# EEG_AFE_Sheet_1.net
KiCad netlist of a schematic drawn in Altium Designer
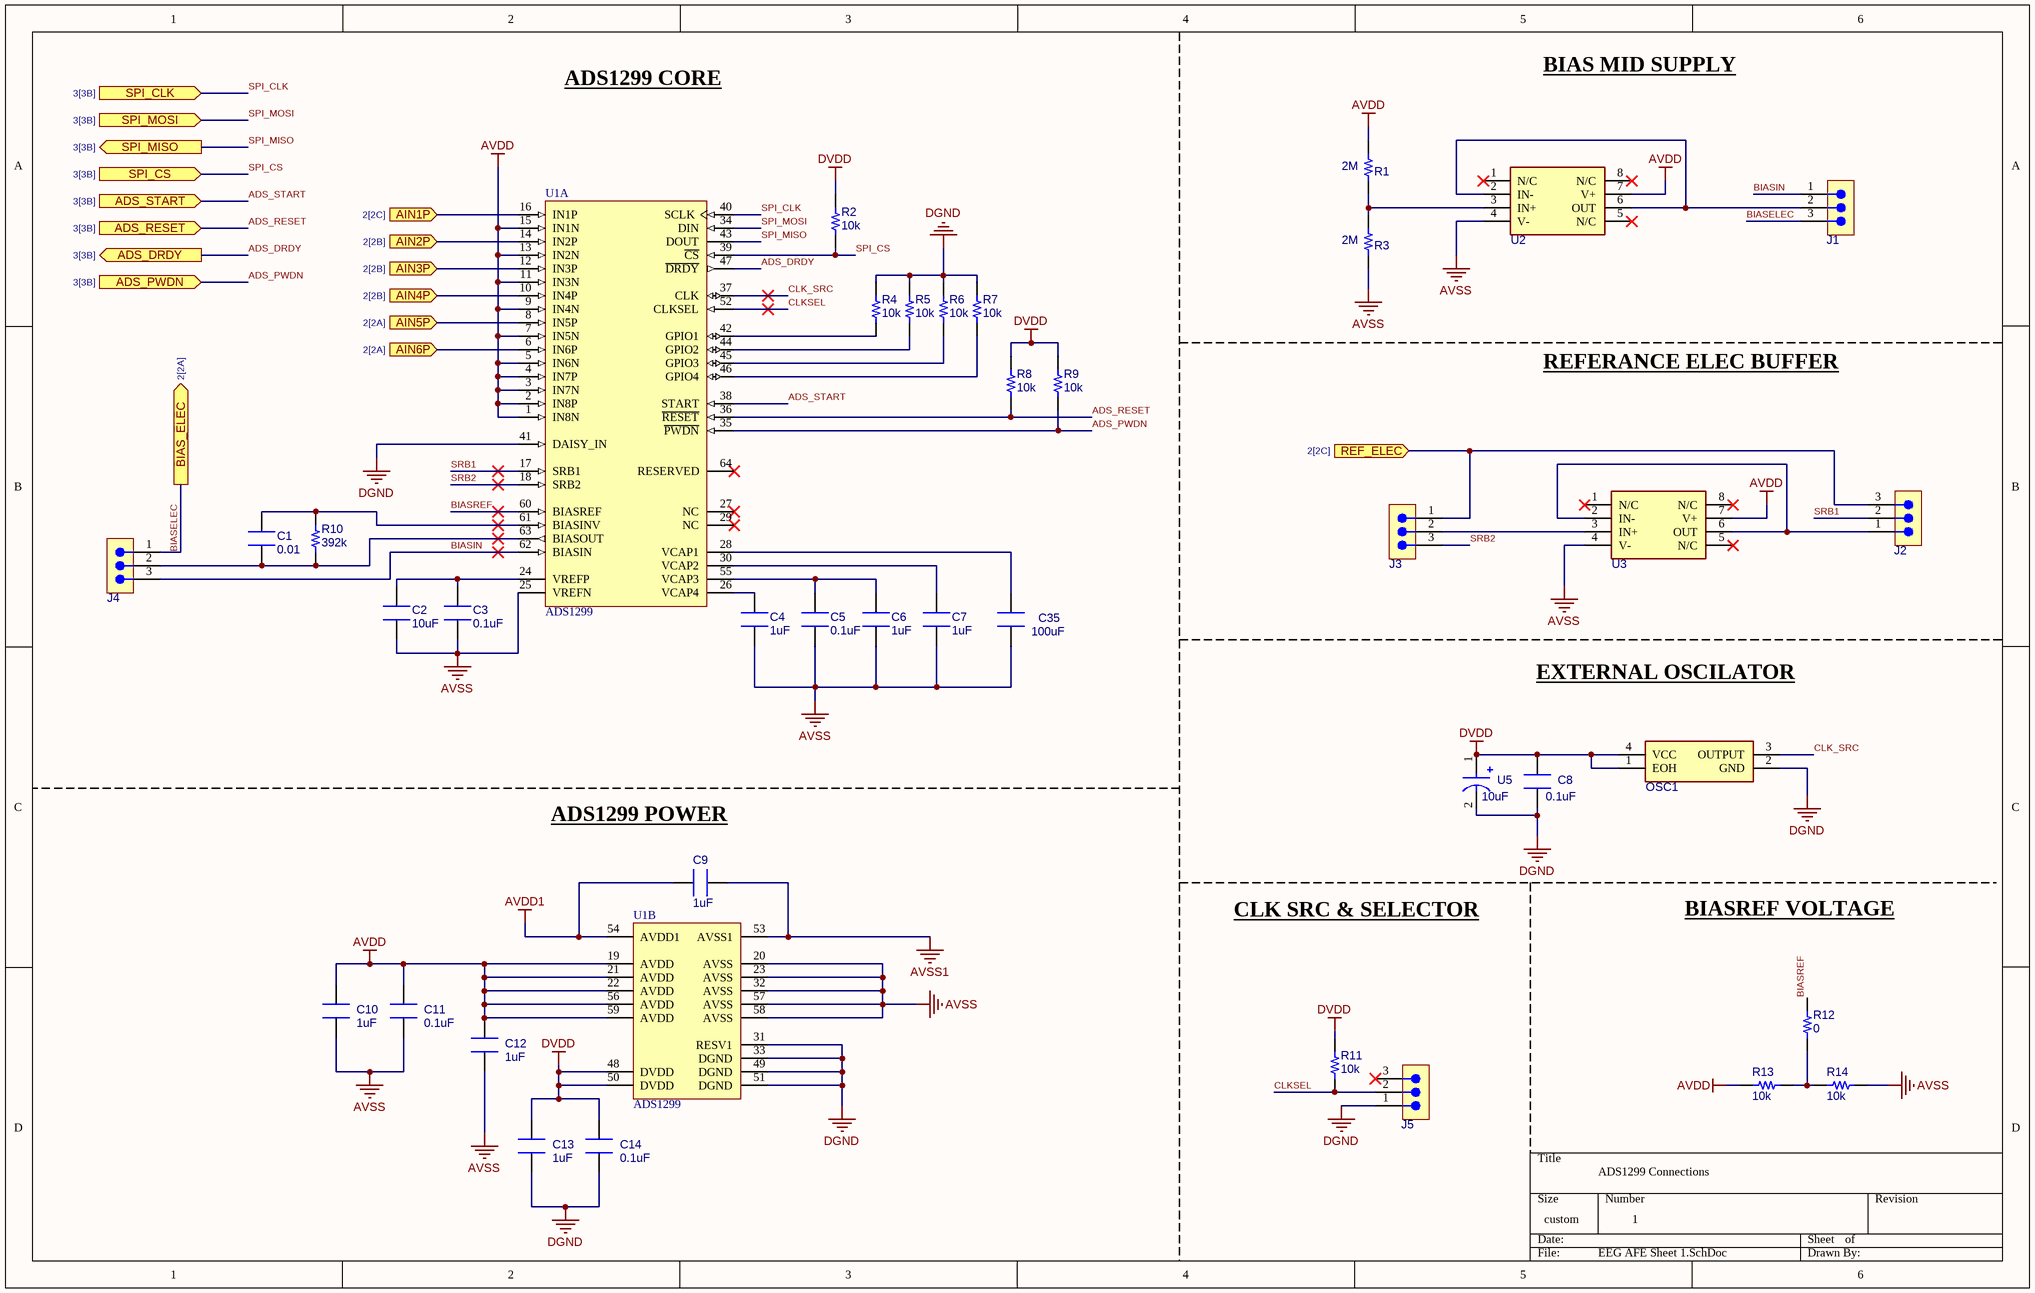
[diagram p0: EEG AFE Sheet 1.SchDoc]

(export (version "E")
  (design (tool "Eeschema 10.0.6"))
  (components
    (comp (ref "C1")
      (value "0.01")
      (footprint "CAP 0603_1608")
      (fields (field (name "MANUFACTURER") "???") (field (name "MANUFACTURER PART NUMBER") "08055C104KAT2A"))
      (libsource (lib "Schlib") (part "08055C104KAT2A"))
    )
    (comp (ref "C2")
      (value "10uF")
      (footprint "CAP0805")
      (fields (field (name "MANUFACTURER") "???") (field (name "MANUFACTURER PART NUMBER") "08055C104KAT2A"))
      (libsource (lib "Schlib") (part "08055C104KAT2A"))
    )
    (comp (ref "C3")
      (value "0.1uF")
      (footprint "CAP 0603_1608")
      (fields (field (name "MANUFACTURER") "???") (field (name "MANUFACTURER PART NUMBER") "08055C104KAT2A"))
      (libsource (lib "Schlib") (part "08055C104KAT2A"))
    )
    (comp (ref "C4")
      (value "1uF")
      (footprint "CAP 0603_1608")
      (fields (field (name "MANUFACTURER") "???") (field (name "MANUFACTURER PART NUMBER") "08055C104KAT2A"))
      (libsource (lib "Schlib") (part "08055C104KAT2A"))
    )
    (comp (ref "C5")
      (value "0.1uF")
      (footprint "CAP 0603_1608")
      (fields (field (name "MANUFACTURER") "???") (field (name "MANUFACTURER PART NUMBER") "08055C104KAT2A"))
      (libsource (lib "Schlib") (part "08055C104KAT2A"))
    )
    (comp (ref "C6")
      (value "1uF")
      (footprint "CAP 0603_1608")
      (fields (field (name "MANUFACTURER") "???") (field (name "MANUFACTURER PART NUMBER") "08055C104KAT2A"))
      (libsource (lib "Schlib") (part "08055C104KAT2A"))
    )
    (comp (ref "C7")
      (value "1uF")
      (footprint "CAP 0603_1608")
      (fields (field (name "MANUFACTURER") "???") (field (name "MANUFACTURER PART NUMBER") "08055C104KAT2A"))
      (libsource (lib "Schlib") (part "08055C104KAT2A"))
    )
    (comp (ref "C8")
      (value "0.1uF")
      (footprint "CAP 0603_1608")
      (fields (field (name "MANUFACTURER") "???") (field (name "MANUFACTURER PART NUMBER") "08055C104KAT2A"))
      (libsource (lib "Schlib") (part "08055C104KAT2A"))
    )
    (comp (ref "C9")
      (value "1uF")
      (footprint "CAP 0603_1608")
      (fields (field (name "MANUFACTURER") "???") (field (name "MANUFACTURER PART NUMBER") "08055C104KAT2A"))
      (libsource (lib "Schlib") (part "08055C104KAT2A"))
    )
    (comp (ref "C10")
      (value "1uF")
      (footprint "CAP 0603_1608")
      (fields (field (name "MANUFACTURER") "???") (field (name "MANUFACTURER PART NUMBER") "08055C104KAT2A"))
      (libsource (lib "Schlib") (part "08055C104KAT2A"))
    )
    (comp (ref "C11")
      (value "0.1uF")
      (footprint "CAP 0603_1608")
      (fields (field (name "MANUFACTURER") "???") (field (name "MANUFACTURER PART NUMBER") "08055C104KAT2A"))
      (libsource (lib "Schlib") (part "08055C104KAT2A"))
    )
    (comp (ref "C12")
      (value "1uF")
      (footprint "CAP 0603_1608")
      (fields (field (name "MANUFACTURER") "???") (field (name "MANUFACTURER PART NUMBER") "08055C104KAT2A"))
      (libsource (lib "Schlib") (part "08055C104KAT2A"))
    )
    (comp (ref "C13")
      (value "1uF")
      (footprint "CAP 0603_1608")
      (fields (field (name "MANUFACTURER") "???") (field (name "MANUFACTURER PART NUMBER") "08055C104KAT2A"))
      (libsource (lib "Schlib") (part "08055C104KAT2A"))
    )
    (comp (ref "C14")
      (value "0.1uF")
      (footprint "CAP 0603_1608")
      (fields (field (name "MANUFACTURER") "???") (field (name "MANUFACTURER PART NUMBER") "08055C104KAT2A"))
      (libsource (lib "Schlib") (part "08055C104KAT2A"))
    )
    (comp (ref "C35")
      (value "100uF")
      (footprint "CAP1210")
      (fields
        (field (name "MANUFACTURER") "???")
        (field (name "MANUFACTURER PART NUMBER") "CL32A107MPVNNNE")
        (field (name "PUBLISHER") "Paraqum Technologies")
      )
      (libsource (lib "Schlib") (part "CL32A107MPVNNNE"))
    )
    (comp (ref "J1")
      (value "*")
      (footprint "SMTC-TSW-103-07-X-S")
      (fields
        (field (name "MANUFACTURER") "???")
        (field (name "MANUFACTURER PART NUMBER") "TSW-103-07-T-S")
        (field (name "PUBLISHER") "Paraqum Technologies")
      )
      (libsource (lib "") (part "TSW-103-07-T-S_2"))
    )
    (comp (ref "J2")
      (value "*")
      (footprint "SMTC-TSW-103-07-X-S")
      (fields
        (field (name "MANUFACTURER") "???")
        (field (name "MANUFACTURER PART NUMBER") "TSW-103-07-T-S")
        (field (name "PUBLISHER") "Paraqum Technologies")
      )
      (libsource (lib "Schlib") (part "TSW-103-07-T-S"))
    )
    (comp (ref "J3")
      (value "*")
      (footprint "SMTC-TSW-103-07-X-S")
      (fields
        (field (name "MANUFACTURER") "???")
        (field (name "MANUFACTURER PART NUMBER") "TSW-103-07-T-S")
        (field (name "PUBLISHER") "Paraqum Technologies")
      )
      (libsource (lib "") (part "TSW-103-07-T-S_1"))
    )
    (comp (ref "J4")
      (value "*")
      (footprint "SMTC-TSW-103-07-X-S")
      (fields
        (field (name "MANUFACTURER") "???")
        (field (name "MANUFACTURER PART NUMBER") "TSW-103-07-T-S")
        (field (name "PUBLISHER") "Paraqum Technologies")
      )
      (libsource (lib "") (part "TSW-103-07-T-S_1"))
    )
    (comp (ref "J5")
      (value "*")
      (footprint "SMTC-TSW-103-07-X-S")
      (fields
        (field (name "MANUFACTURER") "???")
        (field (name "MANUFACTURER PART NUMBER") "TSW-103-07-T-S")
        (field (name "PUBLISHER") "Paraqum Technologies")
      )
      (libsource (lib "Schlib") (part "TSW-103-07-T-S"))
    )
    (comp (ref "OSC1")
      (value "*")
      (footprint "632L3I002M04800")
      (description "Standard Clock Oscillators 2.048MHz 3.3V 50ppm")
      (fields
        (field (name "MANUFACTURER") "???")
        (field (name "MANUFACTURER PART NUMBER") "632L3I002M04800")
        (field (name "PUBLISHER") "Paraqum Technologies")
      )
      (libsource (lib "Schlib") (part "632L3I002M04800"))
    )
    (comp (ref "R1")
      (value "2M")
      (footprint "RES 0603_1608")
      (fields
        (field (name "MANUFACTURER") "???")
        (field (name "MANUFACTURER PART NUMBER") "RC0805FR-0710KL")
        (field (name "PUBLISHER") "Paraqum Technologies")
      )
      (libsource (lib "Schlib") (part "RC0805FR-0710KL"))
    )
    (comp (ref "R2")
      (value "10k")
      (footprint "RES 0603_1608")
      (fields
        (field (name "MANUFACTURER") "???")
        (field (name "MANUFACTURER PART NUMBER") "RC0805FR-0710KL")
        (field (name "PUBLISHER") "Paraqum Technologies")
      )
      (libsource (lib "Schlib") (part "RC0805FR-0710KL"))
    )
    (comp (ref "R3")
      (value "2M")
      (footprint "RES 0603_1608")
      (fields
        (field (name "MANUFACTURER") "???")
        (field (name "MANUFACTURER PART NUMBER") "RC0805FR-0710KL")
        (field (name "PUBLISHER") "Paraqum Technologies")
      )
      (libsource (lib "Schlib") (part "RC0805FR-0710KL"))
    )
    (comp (ref "R4")
      (value "10k")
      (footprint "RES 0603_1608")
      (fields
        (field (name "MANUFACTURER") "???")
        (field (name "MANUFACTURER PART NUMBER") "RC0805FR-0710KL")
        (field (name "PUBLISHER") "Paraqum Technologies")
      )
      (libsource (lib "Schlib") (part "RC0805FR-0710KL"))
    )
    (comp (ref "R5")
      (value "10k")
      (footprint "RES 0603_1608")
      (fields
        (field (name "MANUFACTURER") "???")
        (field (name "MANUFACTURER PART NUMBER") "RC0805FR-0710KL")
        (field (name "PUBLISHER") "Paraqum Technologies")
      )
      (libsource (lib "Schlib") (part "RC0805FR-0710KL"))
    )
    (comp (ref "R6")
      (value "10k")
      (footprint "RES 0603_1608")
      (fields
        (field (name "MANUFACTURER") "???")
        (field (name "MANUFACTURER PART NUMBER") "RC0805FR-0710KL")
        (field (name "PUBLISHER") "Paraqum Technologies")
      )
      (libsource (lib "Schlib") (part "RC0805FR-0710KL"))
    )
    (comp (ref "R7")
      (value "10k")
      (footprint "RES 0603_1608")
      (fields
        (field (name "MANUFACTURER") "???")
        (field (name "MANUFACTURER PART NUMBER") "RC0805FR-0710KL")
        (field (name "PUBLISHER") "Paraqum Technologies")
      )
      (libsource (lib "Schlib") (part "RC0805FR-0710KL"))
    )
    (comp (ref "R8")
      (value "10k")
      (footprint "RES 0603_1608")
      (fields
        (field (name "MANUFACTURER") "???")
        (field (name "MANUFACTURER PART NUMBER") "RC0805FR-0710KL")
        (field (name "PUBLISHER") "Paraqum Technologies")
      )
      (libsource (lib "Schlib") (part "RC0805FR-0710KL"))
    )
    (comp (ref "R9")
      (value "10k")
      (footprint "RES 0603_1608")
      (fields
        (field (name "MANUFACTURER") "???")
        (field (name "MANUFACTURER PART NUMBER") "RC0805FR-0710KL")
        (field (name "PUBLISHER") "Paraqum Technologies")
      )
      (libsource (lib "Schlib") (part "RC0805FR-0710KL"))
    )
    (comp (ref "R10")
      (value "392k")
      (footprint "RES 0603_1608")
      (fields
        (field (name "MANUFACTURER") "???")
        (field (name "MANUFACTURER PART NUMBER") "RC0805FR-0710KL")
        (field (name "PUBLISHER") "Paraqum Technologies")
      )
      (libsource (lib "Schlib") (part "RC0805FR-0710KL"))
    )
    (comp (ref "R11")
      (value "10k")
      (footprint "RES 0603_1608")
      (fields
        (field (name "MANUFACTURER") "???")
        (field (name "MANUFACTURER PART NUMBER") "RC0805FR-0710KL")
        (field (name "PUBLISHER") "Paraqum Technologies")
      )
      (libsource (lib "Schlib") (part "RC0805FR-0710KL"))
    )
    (comp (ref "R12")
      (value "0")
      (footprint "RES 0603_1608")
      (fields
        (field (name "MANUFACTURER") "???")
        (field (name "MANUFACTURER PART NUMBER") "RC0805FR-0710KL")
        (field (name "PUBLISHER") "Paraqum Technologies")
      )
      (libsource (lib "Schlib") (part "RC0805FR-0710KL"))
    )
    (comp (ref "R13")
      (value "10k")
      (footprint "RES 0603_1608")
      (fields
        (field (name "MANUFACTURER") "???")
        (field (name "MANUFACTURER PART NUMBER") "RC0805FR-0710KL")
        (field (name "PUBLISHER") "Paraqum Technologies")
      )
      (libsource (lib "Schlib") (part "RC0805FR-0710KL"))
    )
    (comp (ref "R14")
      (value "10k")
      (footprint "RES 0603_1608")
      (fields
        (field (name "MANUFACTURER") "???")
        (field (name "MANUFACTURER PART NUMBER") "RC0805FR-0710KL")
        (field (name "PUBLISHER") "Paraqum Technologies")
      )
      (libsource (lib "Schlib") (part "RC0805FR-0710KL"))
    )
    (comp (ref "U1")
      (value "ADS1299")
      (footprint "TI-PAG64_N")
      (libsource (lib "") (part "TI-ADS1299-PAG-64_1"))
    )
    (comp (ref "U2")
      (value "*")
      (footprint "SOIC127P600X175-8N")
      (description "Operational Amplifier, 1 Func, 25uV Offset-Max, CMOS, PDSO8")
      (fields
        (field (name "MANUFACTURER") "???")
        (field (name "MANUFACTURER PART NUMBER") "OPA376AIDR")
        (field (name "PUBLISHER") "Paraqum Technologies")
      )
      (libsource (lib "Schlib") (part "OPA376AIDR"))
    )
    (comp (ref "U3")
      (value "*")
      (footprint "SOIC127P600X175-8N")
      (description "Operational Amplifier, 1 Func, 25uV Offset-Max, CMOS, PDSO8")
      (fields
        (field (name "MANUFACTURER") "???")
        (field (name "MANUFACTURER PART NUMBER") "OPA376AIDR")
        (field (name "PUBLISHER") "Paraqum Technologies")
      )
      (libsource (lib "Schlib") (part "OPA376AIDR"))
    )
    (comp (ref "U5")
      (value "10uF")
      (footprint "CAPC0805_TANT")
      (fields
        (field (name "MANUFACTURER") "???")
        (field (name "MANUFACTURER PART NUMBER") "TPSR105K025R4000")
        (field (name "PUBLISHER") "Paraqum Technologies")
      )
      (libsource (lib "Schlib") (part "TPSR105K025R4000"))
    )
  )
  (nets
    (net (code "1") (name "/ADS_DRDY") (class "Default")
      (node (ref "U1") (pin "47") (pinfunction "~{DRDY}_47") (pintype "output"))
    )
    (net (code "2") (name "/ADS_PWDN") (class "Default")
      (node (ref "R9") (pin "2") (pinfunction "2_2") (pintype "passive"))
      (node (ref "U1") (pin "35") (pinfunction "~{PWDN}_35") (pintype "input"))
    )
    (net (code "3") (name "/ADS_RESET") (class "Default")
      (node (ref "R8") (pin "2") (pinfunction "2_2") (pintype "passive"))
      (node (ref "U1") (pin "36") (pinfunction "~{RESET}_36") (pintype "input"))
    )
    (net (code "4") (name "/ADS_START") (class "Default")
      (node (ref "U1") (pin "38") (pinfunction "START_38") (pintype "input"))
    )
    (net (code "5") (name "/AIN1P") (class "Default")
      (node (ref "U1") (pin "16") (pinfunction "IN1P_16") (pintype "input"))
    )
    (net (code "6") (name "/AIN2P") (class "Default")
      (node (ref "U1") (pin "14") (pinfunction "IN2P_14") (pintype "input"))
    )
    (net (code "7") (name "/AIN3P") (class "Default")
      (node (ref "U1") (pin "12") (pinfunction "IN3P_12") (pintype "input"))
    )
    (net (code "8") (name "/AIN4P") (class "Default")
      (node (ref "U1") (pin "10") (pinfunction "IN4P_10") (pintype "input"))
    )
    (net (code "9") (name "/AIN5P") (class "Default")
      (node (ref "U1") (pin "8") (pinfunction "IN5P_8") (pintype "input"))
    )
    (net (code "10") (name "/AIN6P") (class "Default")
      (node (ref "U1") (pin "6") (pinfunction "IN6P_6") (pintype "input"))
    )
    (net (code "11") (name "/BIASELEC") (class "Default")
      (node (ref "J1") (pin "3") (pinfunction "3_3") (pintype "passive"))
      (node (ref "J4") (pin "1") (pinfunction "1_1") (pintype "passive"))
    )
    (net (code "12") (name "/BIASIN") (class "Default")
      (node (ref "J1") (pin "1") (pinfunction "1_1") (pintype "passive"))
      (node (ref "J4") (pin "3") (pinfunction "3_3") (pintype "passive"))
      (node (ref "U1") (pin "62") (pinfunction "BIASIN_62") (pintype "input"))
    )
    (net (code "13") (name "/BIASREF") (class "Default")
      (node (ref "R12") (pin "1") (pinfunction "1_1") (pintype "passive"))
      (node (ref "U1") (pin "60") (pinfunction "BIASREF_60") (pintype "input"))
    )
    (net (code "14") (name "/CLKSEL") (class "Default")
      (node (ref "J5") (pin "2") (pinfunction "2_2") (pintype "passive"))
      (node (ref "R11") (pin "1") (pinfunction "1_1") (pintype "passive"))
      (node (ref "U1") (pin "52") (pinfunction "CLKSEL_52") (pintype "input"))
    )
    (net (code "15") (name "/CLK_SRC") (class "Default")
      (node (ref "OSC1") (pin "3") (pinfunction "OUTPUT_3") (pintype "passive"))
      (node (ref "U1") (pin "37") (pinfunction "CLK_37") (pintype "bidirectional"))
    )
    (net (code "16") (name "/REF_ELEC") (class "Default")
      (node (ref "J2") (pin "3") (pinfunction "3_3") (pintype "passive"))
      (node (ref "J3") (pin "1") (pinfunction "1_1") (pintype "passive"))
    )
    (net (code "17") (name "/SPI_CLK") (class "Default")
      (node (ref "U1") (pin "40") (pinfunction "SCLK_40") (pintype "input"))
    )
    (net (code "18") (name "/SPI_CS") (class "Default")
      (node (ref "R2") (pin "1") (pinfunction "1_1") (pintype "passive"))
      (node (ref "U1") (pin "39") (pinfunction "~{CS}_39") (pintype "input"))
    )
    (net (code "19") (name "/SPI_MISO") (class "Default")
      (node (ref "U1") (pin "43") (pinfunction "DOUT_43") (pintype "tri_state"))
    )
    (net (code "20") (name "/SPI_MOSI") (class "Default")
      (node (ref "U1") (pin "34") (pinfunction "DIN_34") (pintype "input"))
    )
    (net (code "21") (name "/SRB1") (class "Default")
      (node (ref "J2") (pin "2") (pinfunction "2_2") (pintype "passive"))
      (node (ref "U1") (pin "17") (pinfunction "SRB1_17") (pintype "input"))
    )
    (net (code "22") (name "/SRB2") (class "Default")
      (node (ref "J3") (pin "3") (pinfunction "3_3") (pintype "passive"))
      (node (ref "U1") (pin "18") (pinfunction "SRB2_18") (pintype "input"))
    )
    (net (code "23") (name "AVDD") (class "Default")
      (node (ref "C10") (pin "2") (pinfunction "2_2") (pintype "passive"))
      (node (ref "C11") (pin "2") (pinfunction "2_2") (pintype "passive"))
      (node (ref "C12") (pin "2") (pinfunction "2_2") (pintype "passive"))
      (node (ref "R1") (pin "2") (pinfunction "2_2") (pintype "passive"))
      (node (ref "R13") (pin "2") (pinfunction "2_2") (pintype "passive"))
      (node (ref "U1") (pin "1") (pinfunction "IN8N_1") (pintype "input"))
      (node (ref "U1") (pin "11") (pinfunction "IN3N_11") (pintype "input"))
      (node (ref "U1") (pin "13") (pinfunction "IN2N_13") (pintype "input"))
      (node (ref "U1") (pin "15") (pinfunction "IN1N_15") (pintype "input"))
      (node (ref "U1") (pin "19") (pinfunction "AVDD_19") (pintype "power_in"))
      (node (ref "U1") (pin "2") (pinfunction "IN8P_2") (pintype "input"))
      (node (ref "U1") (pin "21") (pinfunction "AVDD_21") (pintype "power_in"))
      (node (ref "U1") (pin "22") (pinfunction "AVDD_22") (pintype "power_in"))
      (node (ref "U1") (pin "3") (pinfunction "IN7N_3") (pintype "input"))
      (node (ref "U1") (pin "4") (pinfunction "IN7P_4") (pintype "input"))
      (node (ref "U1") (pin "5") (pinfunction "IN6N_5") (pintype "input"))
      (node (ref "U1") (pin "56") (pinfunction "AVDD_56") (pintype "power_in"))
      (node (ref "U1") (pin "59") (pinfunction "AVDD_59") (pintype "power_in"))
      (node (ref "U1") (pin "7") (pinfunction "IN5N_7") (pintype "input"))
      (node (ref "U1") (pin "9") (pinfunction "IN4N_9") (pintype "input"))
      (node (ref "U2") (pin "7") (pinfunction "V+_7") (pintype "passive"))
      (node (ref "U3") (pin "7") (pinfunction "V+_7") (pintype "passive"))
    )
    (net (code "24") (name "AVDD1") (class "Default")
      (node (ref "C9") (pin "2") (pinfunction "2_2") (pintype "passive"))
      (node (ref "U1") (pin "54") (pinfunction "AVDD1_54") (pintype "power_in"))
    )
    (net (code "25") (name "AVSS") (class "Default")
      (node (ref "C10") (pin "1") (pinfunction "1_1") (pintype "passive"))
      (node (ref "C11") (pin "1") (pinfunction "1_1") (pintype "passive"))
      (node (ref "C12") (pin "1") (pinfunction "1_1") (pintype "passive"))
      (node (ref "C2") (pin "2") (pinfunction "2_2") (pintype "passive"))
      (node (ref "C3") (pin "2") (pinfunction "2_2") (pintype "passive"))
      (node (ref "C35") (pin "1") (pinfunction "1_1") (pintype "passive"))
      (node (ref "C4") (pin "2") (pinfunction "2_2") (pintype "passive"))
      (node (ref "C5") (pin "2") (pinfunction "2_2") (pintype "passive"))
      (node (ref "C6") (pin "2") (pinfunction "2_2") (pintype "passive"))
      (node (ref "C7") (pin "2") (pinfunction "2_2") (pintype "passive"))
      (node (ref "R14") (pin "1") (pinfunction "1_1") (pintype "passive"))
      (node (ref "R3") (pin "1") (pinfunction "1_1") (pintype "passive"))
      (node (ref "U1") (pin "20") (pinfunction "AVSS_20") (pintype "power_in"))
      (node (ref "U1") (pin "23") (pinfunction "AVSS_23") (pintype "power_in"))
      (node (ref "U1") (pin "25") (pinfunction "VREFN_25") (pintype "passive"))
      (node (ref "U1") (pin "32") (pinfunction "AVSS_32") (pintype "power_in"))
      (node (ref "U1") (pin "57") (pinfunction "AVSS_57") (pintype "power_in"))
      (node (ref "U1") (pin "58") (pinfunction "AVSS_58") (pintype "power_in"))
      (node (ref "U2") (pin "4") (pinfunction "V-_4") (pintype "passive"))
      (node (ref "U3") (pin "4") (pinfunction "V-_4") (pintype "passive"))
    )
    (net (code "26") (name "AVSS1") (class "Default")
      (node (ref "C9") (pin "1") (pinfunction "1_1") (pintype "passive"))
      (node (ref "U1") (pin "53") (pinfunction "AVSS1_53") (pintype "power_in"))
    )
    (net (code "27") (name "DGND") (class "Default")
      (node (ref "C13") (pin "1") (pinfunction "1_1") (pintype "passive"))
      (node (ref "C14") (pin "1") (pinfunction "1_1") (pintype "passive"))
      (node (ref "C8") (pin "1") (pinfunction "1_1") (pintype "passive"))
      (node (ref "J5") (pin "1") (pinfunction "1_1") (pintype "passive"))
      (node (ref "OSC1") (pin "2") (pinfunction "GND_2") (pintype "passive"))
      (node (ref "R4") (pin "2") (pinfunction "2_2") (pintype "passive"))
      (node (ref "R5") (pin "2") (pinfunction "2_2") (pintype "passive"))
      (node (ref "R6") (pin "2") (pinfunction "2_2") (pintype "passive"))
      (node (ref "R7") (pin "2") (pinfunction "2_2") (pintype "passive"))
      (node (ref "U1") (pin "31") (pinfunction "RESV1_31") (pintype "power_in"))
      (node (ref "U1") (pin "33") (pinfunction "DGND_33") (pintype "power_in"))
      (node (ref "U1") (pin "41") (pinfunction "DAISY_IN_41") (pintype "input"))
      (node (ref "U1") (pin "49") (pinfunction "DGND_49") (pintype "power_in"))
      (node (ref "U1") (pin "51") (pinfunction "DGND_51") (pintype "power_in"))
      (node (ref "U5") (pin "2") (pinfunction "A_2") (pintype "passive"))
    )
    (net (code "28") (name "DVDD") (class "Default")
      (node (ref "C13") (pin "2") (pinfunction "2_2") (pintype "passive"))
      (node (ref "C14") (pin "2") (pinfunction "2_2") (pintype "passive"))
      (node (ref "C8") (pin "2") (pinfunction "2_2") (pintype "passive"))
      (node (ref "OSC1") (pin "1") (pinfunction "EOH_1") (pintype "passive"))
      (node (ref "OSC1") (pin "4") (pinfunction "VCC_4") (pintype "passive"))
      (node (ref "R11") (pin "2") (pinfunction "2_2") (pintype "passive"))
      (node (ref "R2") (pin "2") (pinfunction "2_2") (pintype "passive"))
      (node (ref "R8") (pin "1") (pinfunction "1_1") (pintype "passive"))
      (node (ref "R9") (pin "1") (pinfunction "1_1") (pintype "passive"))
      (node (ref "U1") (pin "48") (pinfunction "DVDD_48") (pintype "power_in"))
      (node (ref "U1") (pin "50") (pinfunction "DVDD_50") (pintype "power_in"))
      (node (ref "U5") (pin "1") (pinfunction "C_1") (pintype "passive"))
    )
    (net (code "29") (name "Net-(R12-Pad2)") (class "Default")
      (node (ref "R12") (pin "2") (pinfunction "2_2") (pintype "passive"))
      (node (ref "R13") (pin "1") (pinfunction "1_1") (pintype "passive"))
      (node (ref "R14") (pin "2") (pinfunction "2_2") (pintype "passive"))
    )
    (net (code "30") (name "Net-(U1A-BIASINV)") (class "Default")
      (node (ref "C1") (pin "1") (pinfunction "1_1") (pintype "passive"))
      (node (ref "R10") (pin "1") (pinfunction "1_1") (pintype "passive"))
      (node (ref "U1") (pin "61") (pinfunction "BIASINV_61") (pintype "input"))
    )
    (net (code "31") (name "Net-(U1A-BIASOUT)") (class "Default")
      (node (ref "C1") (pin "2") (pinfunction "2_2") (pintype "passive"))
      (node (ref "J4") (pin "2") (pinfunction "2_2") (pintype "passive"))
      (node (ref "R10") (pin "2") (pinfunction "2_2") (pintype "passive"))
      (node (ref "U1") (pin "63") (pinfunction "BIASOUT_63") (pintype "output"))
    )
    (net (code "32") (name "Net-(U1A-GPIO1)") (class "Default")
      (node (ref "R4") (pin "1") (pinfunction "1_1") (pintype "passive"))
      (node (ref "U1") (pin "42") (pinfunction "GPIO1_42") (pintype "bidirectional"))
    )
    (net (code "33") (name "Net-(U1A-GPIO2)") (class "Default")
      (node (ref "R5") (pin "1") (pinfunction "1_1") (pintype "passive"))
      (node (ref "U1") (pin "44") (pinfunction "GPIO2_44") (pintype "bidirectional"))
    )
    (net (code "34") (name "Net-(U1A-GPIO3)") (class "Default")
      (node (ref "R6") (pin "1") (pinfunction "1_1") (pintype "passive"))
      (node (ref "U1") (pin "45") (pinfunction "GPIO3_45") (pintype "bidirectional"))
    )
    (net (code "35") (name "Net-(U1A-GPIO4)") (class "Default")
      (node (ref "R7") (pin "1") (pinfunction "1_1") (pintype "passive"))
      (node (ref "U1") (pin "46") (pinfunction "GPIO4_46") (pintype "bidirectional"))
    )
    (net (code "36") (name "Net-(U1A-VCAP1)") (class "Default")
      (node (ref "C35") (pin "2") (pinfunction "2_2") (pintype "passive"))
      (node (ref "U1") (pin "28") (pinfunction "VCAP1_28") (pintype "passive"))
    )
    (net (code "37") (name "Net-(U1A-VCAP2)") (class "Default")
      (node (ref "C7") (pin "1") (pinfunction "1_1") (pintype "passive"))
      (node (ref "U1") (pin "30") (pinfunction "VCAP2_30") (pintype "passive"))
    )
    (net (code "38") (name "Net-(U1A-VCAP3)") (class "Default")
      (node (ref "C5") (pin "1") (pinfunction "1_1") (pintype "passive"))
      (node (ref "C6") (pin "1") (pinfunction "1_1") (pintype "passive"))
      (node (ref "U1") (pin "55") (pinfunction "VCAP3_55") (pintype "passive"))
    )
    (net (code "39") (name "Net-(U1A-VCAP4)") (class "Default")
      (node (ref "C4") (pin "1") (pinfunction "1_1") (pintype "passive"))
      (node (ref "U1") (pin "26") (pinfunction "VCAP4_26") (pintype "passive"))
    )
    (net (code "40") (name "Net-(U1A-VREFP)") (class "Default")
      (node (ref "C2") (pin "1") (pinfunction "1_1") (pintype "passive"))
      (node (ref "C3") (pin "1") (pinfunction "1_1") (pintype "passive"))
      (node (ref "U1") (pin "24") (pinfunction "VREFP_24") (pintype "passive"))
    )
    (net (code "41") (name "Net-(U2-IN+)") (class "Default")
      (node (ref "R1") (pin "1") (pinfunction "1_1") (pintype "passive"))
      (node (ref "R3") (pin "2") (pinfunction "2_2") (pintype "passive"))
      (node (ref "U2") (pin "3") (pinfunction "IN+_3") (pintype "passive"))
    )
    (net (code "42") (name "Net-(U2-IN-)") (class "Default")
      (node (ref "J1") (pin "2") (pinfunction "2_2") (pintype "passive"))
      (node (ref "U2") (pin "2") (pinfunction "IN-_2") (pintype "passive"))
      (node (ref "U2") (pin "6") (pinfunction "OUT_6") (pintype "passive"))
    )
    (net (code "43") (name "Net-(U3-IN+)") (class "Default")
      (node (ref "J3") (pin "2") (pinfunction "2_2") (pintype "passive"))
      (node (ref "U3") (pin "3") (pinfunction "IN+_3") (pintype "passive"))
    )
    (net (code "44") (name "Net-(U3-IN-)") (class "Default")
      (node (ref "J2") (pin "1") (pinfunction "1_1") (pintype "passive"))
      (node (ref "U3") (pin "2") (pinfunction "IN-_2") (pintype "passive"))
      (node (ref "U3") (pin "6") (pinfunction "OUT_6") (pintype "passive"))
    )
    (net (code "45") (name "unconnected-(J5-Pad3)") (class "Default")
      (node (ref "J5") (pin "3") (pinfunction "3_3") (pintype "passive+no_connect"))
    )
    (net (code "46") (name "unconnected-(U1A-NC-Pad27)") (class "Default")
      (node (ref "U1") (pin "27") (pinfunction "NC_27") (pintype "passive+no_connect"))
    )
    (net (code "47") (name "unconnected-(U1A-NC-Pad29)") (class "Default")
      (node (ref "U1") (pin "29") (pinfunction "NC_29") (pintype "passive+no_connect"))
    )
    (net (code "48") (name "unconnected-(U1A-RESERVED-Pad64)") (class "Default")
      (node (ref "U1") (pin "64") (pinfunction "RESERVED_64") (pintype "passive+no_connect"))
    )
    (net (code "49") (name "unconnected-(U2-N{slash}C-Pad1)") (class "Default")
      (node (ref "U2") (pin "1") (pinfunction "N/C_1") (pintype "passive+no_connect"))
    )
    (net (code "50") (name "unconnected-(U2-N{slash}C-Pad5)") (class "Default")
      (node (ref "U2") (pin "5") (pinfunction "N/C_5") (pintype "passive+no_connect"))
    )
    (net (code "51") (name "unconnected-(U2-N{slash}C-Pad8)") (class "Default")
      (node (ref "U2") (pin "8") (pinfunction "N/C_8") (pintype "passive+no_connect"))
    )
    (net (code "52") (name "unconnected-(U3-N{slash}C-Pad1)") (class "Default")
      (node (ref "U3") (pin "1") (pinfunction "N/C_1") (pintype "passive+no_connect"))
    )
    (net (code "53") (name "unconnected-(U3-N{slash}C-Pad5)") (class "Default")
      (node (ref "U3") (pin "5") (pinfunction "N/C_5") (pintype "passive+no_connect"))
    )
    (net (code "54") (name "unconnected-(U3-N{slash}C-Pad8)") (class "Default")
      (node (ref "U3") (pin "8") (pinfunction "N/C_8") (pintype "passive+no_connect"))
    )
  )
)
